# circuitdraft.net
KiCad netlist of a schematic drawn in EAGLE
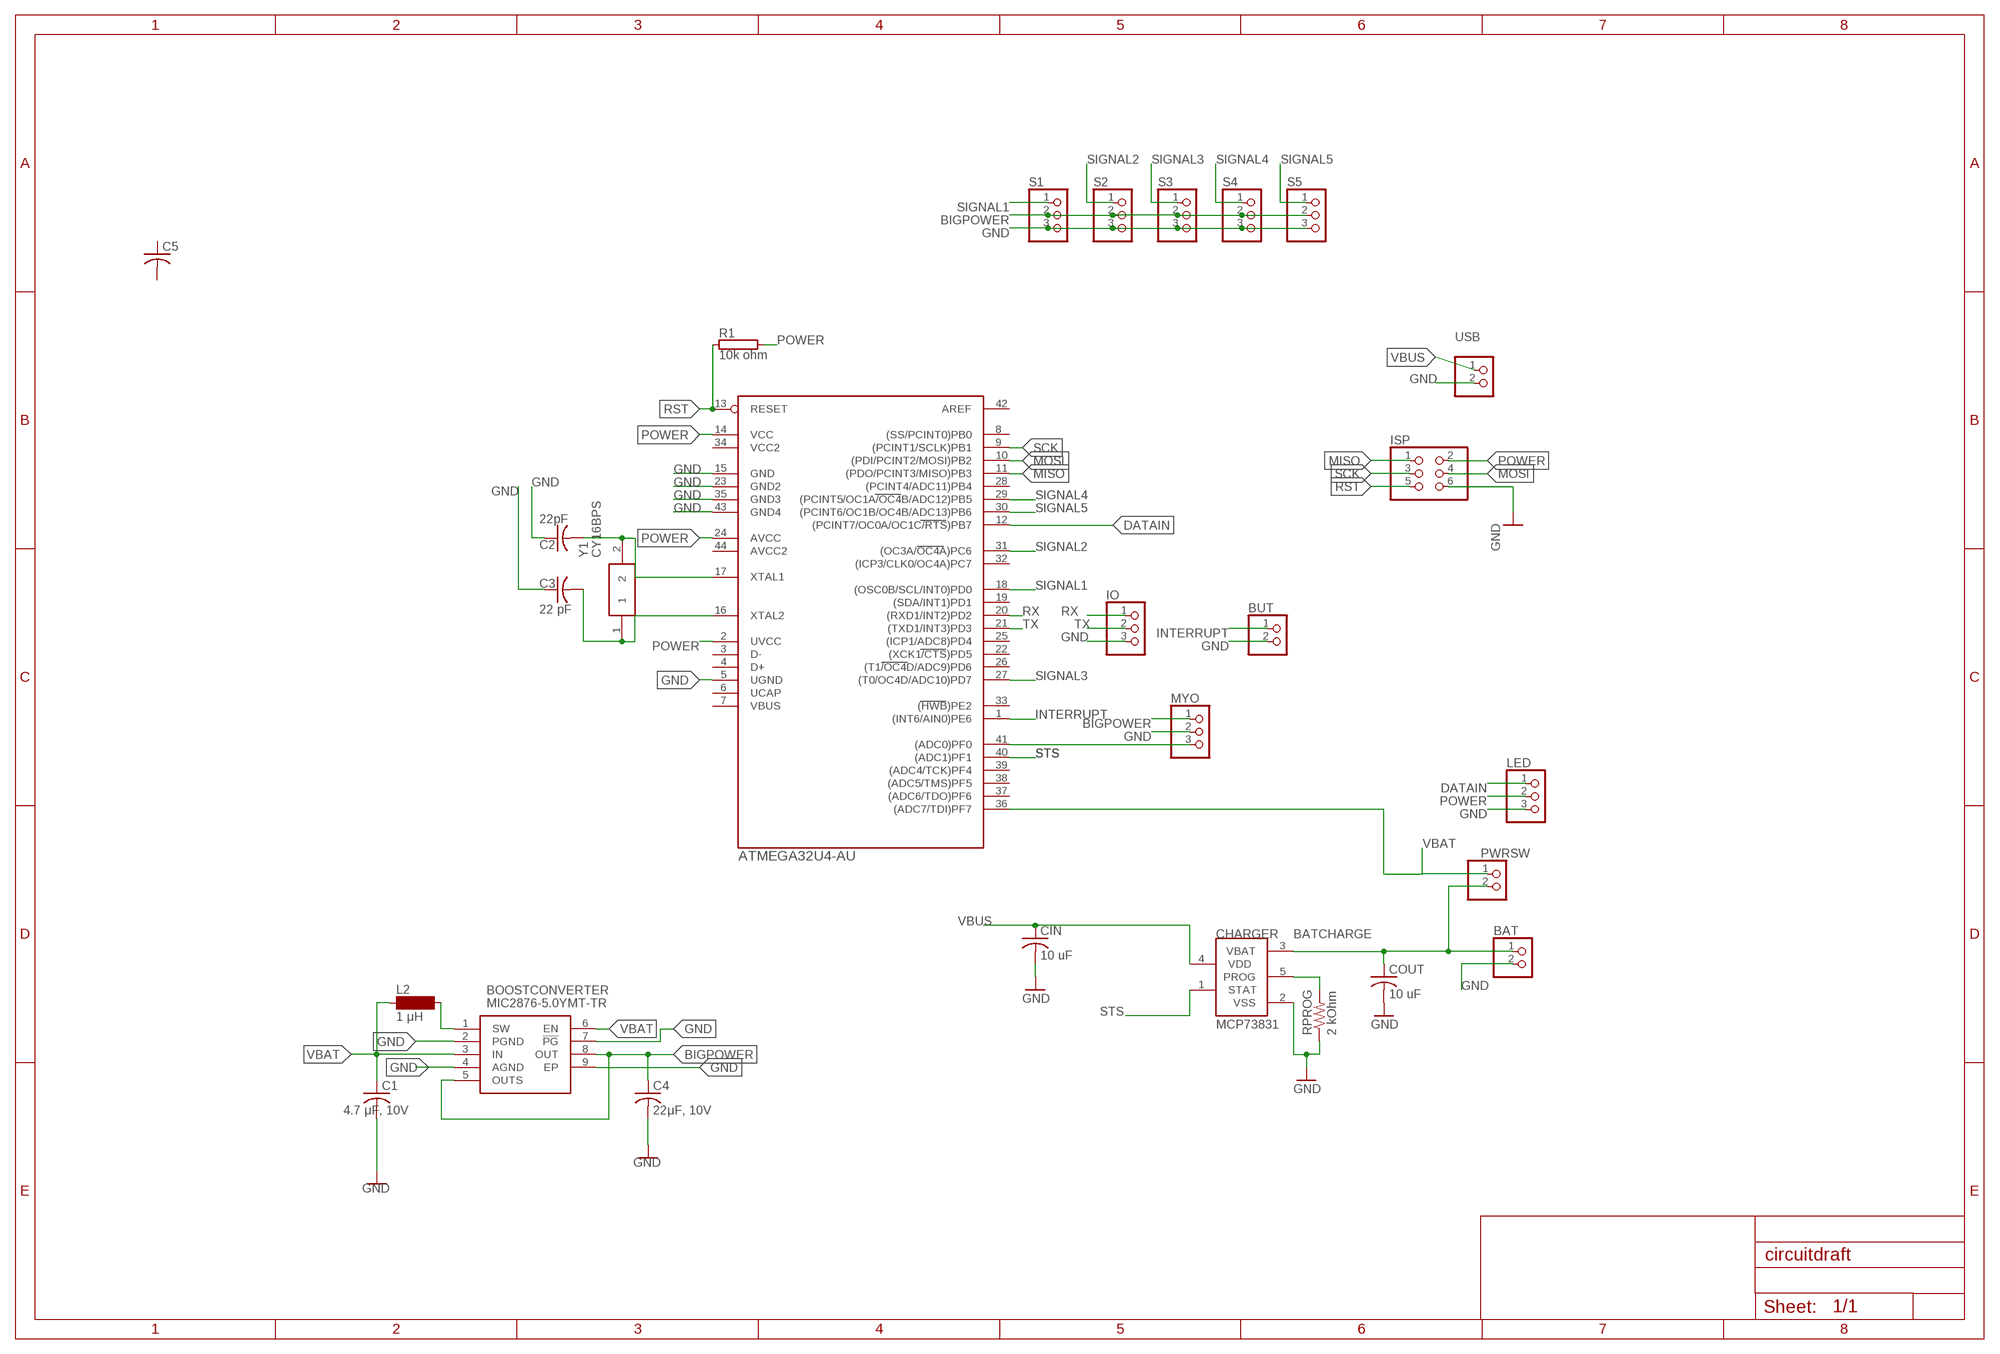
[diagram p0: schematic, sheet 1]

(export (version "E")
  (design (tool "Eeschema 10.0.6"))
  (components
    (comp (ref "BAT")
      (value "PINHD-1X2")
      (footprint "eagle-import:1X02")
      (libsource (lib "eagle-import") (part "PINHD-1X2"))
    )
    (comp (ref "BOOSTCONVERTER")
      (value "MIC2876-5.0YMT-TR")
      (footprint "eagle-import:MIC287650YMTTR")
      (fields (field (name "MOUSER_PART_NUMBER") "998-MIC2876-50YMTTR"))
      (libsource (lib "eagle-import") (part "MIC2876-5.0YMT-TR"))
    )
    (comp (ref "BUT")
      (value "PINHD-1X2")
      (footprint "eagle-import:1X02")
      (libsource (lib "eagle-import") (part "PINHD-1X2"))
    )
    (comp (ref "C1")
      (value "4.7 μF, 10V")
      (footprint "eagle-import:C0603")
      (libsource (lib "eagle-import") (part "C-USC0603"))
    )
    (comp (ref "C2")
      (value "22pF")
      (footprint "eagle-import:C025-024X044")
      (libsource (lib "eagle-import") (part "C-US025-024X044"))
    )
    (comp (ref "C3")
      (value "22 pF")
      (footprint "eagle-import:C025-024X044")
      (libsource (lib "eagle-import") (part "C-US025-024X044"))
    )
    (comp (ref "C4")
      (value "22μF, 10V")
      (footprint "eagle-import:C0603")
      (libsource (lib "eagle-import") (part "C-USC0603"))
    )
    (comp (ref "C5")
      (value "C-USC0603")
      (footprint "eagle-import:C0603")
      (libsource (lib "eagle-import") (part "C-USC0603"))
    )
    (comp (ref "CHARGER")
      (value "MCP73831")
      (footprint "eagle-import:SOT23-5L")
      (libsource (lib "eagle-import") (part "MCP73831"))
    )
    (comp (ref "CIN")
      (value "10 uF")
      (footprint "eagle-import:C0603")
      (libsource (lib "eagle-import") (part "C-USC0603"))
    )
    (comp (ref "COUT")
      (value "10 uF")
      (footprint "eagle-import:C0603")
      (libsource (lib "eagle-import") (part "C-USC0603"))
    )
    (comp (ref "IO")
      (value "PINHD-1X3")
      (footprint "eagle-import:1X03")
      (libsource (lib "eagle-import") (part "PINHD-1X3"))
    )
    (comp (ref "ISP")
      (value "PINHD-2X3")
      (footprint "eagle-import:2X03")
      (libsource (lib "eagle-import") (part "PINHD-2X3"))
    )
    (comp (ref "L2")
      (value "1 μH")
      (footprint "eagle-import:SD75")
      (libsource (lib "eagle-import") (part "SD75"))
    )
    (comp (ref "LED")
      (value "PINHD-1X3")
      (footprint "eagle-import:1X03")
      (libsource (lib "eagle-import") (part "PINHD-1X3"))
    )
    (comp (ref "MYO")
      (value "PINHD-1X3")
      (footprint "eagle-import:1X03")
      (libsource (lib "eagle-import") (part "PINHD-1X3"))
    )
    (comp (ref "PWRSW")
      (value "PINHD-1X2")
      (footprint "eagle-import:1X02")
      (libsource (lib "eagle-import") (part "PINHD-1X2"))
    )
    (comp (ref "R1")
      (value "10k ohm")
      (footprint "eagle-import:RS1_8")
      (libsource (lib "eagle-import") (part "RRS1/8"))
    )
    (comp (ref "RPROG")
      (value "2 kOhm")
      (footprint "eagle-import:R0603")
      (libsource (lib "eagle-import") (part "R-US_R0603"))
    )
    (comp (ref "S1")
      (value "PINHD-1X3")
      (footprint "eagle-import:1X03")
      (libsource (lib "eagle-import") (part "PINHD-1X3"))
    )
    (comp (ref "S2")
      (value "PINHD-1X3")
      (footprint "eagle-import:1X03")
      (libsource (lib "eagle-import") (part "PINHD-1X3"))
    )
    (comp (ref "S3")
      (value "PINHD-1X3")
      (footprint "eagle-import:1X03")
      (libsource (lib "eagle-import") (part "PINHD-1X3"))
    )
    (comp (ref "S4")
      (value "PINHD-1X3")
      (footprint "eagle-import:1X03")
      (libsource (lib "eagle-import") (part "PINHD-1X3"))
    )
    (comp (ref "S5")
      (value "PINHD-1X3")
      (footprint "eagle-import:1X03")
      (libsource (lib "eagle-import") (part "PINHD-1X3"))
    )
    (comp (ref "U$1")
      (value "ATMEGA32U4-AU")
      (footprint "eagle-import:TQFP44")
      (libsource (lib "eagle-import") (part "ATMEGA32U4-AU"))
    )
    (comp (ref "USB")
      (value "PINHD-1X2")
      (footprint "eagle-import:1X02")
      (libsource (lib "eagle-import") (part "PINHD-1X2"))
    )
    (comp (ref "Y1")
      (value "CY16BPS")
      (footprint "eagle-import:CY16BPS")
      (fields (field (name "MOUSER_PART_NUMBER") "549-CY16BPS"))
      (libsource (lib "eagle-import") (part "CY16BPS"))
    )
  )
  (nets
    (net (code "1") (name "/BATCHARGE") (class "Default")
      (node (ref "BAT") (pin "1") (pinfunction "1_1") (pintype "passive"))
      (node (ref "CHARGER") (pin "3") (pinfunction "VBAT_3") (pintype "bidirectional"))
      (node (ref "COUT") (pin "1") (pinfunction "1_1") (pintype "passive"))
      (node (ref "PWRSW") (pin "2") (pinfunction "2_2") (pintype "passive"))
    )
    (net (code "2") (name "/INTERRUPT") (class "Default")
      (node (ref "BUT") (pin "1") (pinfunction "1_1") (pintype "passive"))
      (node (ref "U$1") (pin "1") (pinfunction "(INT6/AIN0)PE6_1") (pintype "bidirectional"))
    )
    (net (code "3") (name "/RX") (class "Default")
      (node (ref "IO") (pin "1") (pinfunction "1_1") (pintype "passive"))
      (node (ref "U$1") (pin "20") (pinfunction "(RXD1/INT2)PD2_20") (pintype "bidirectional"))
    )
    (net (code "4") (name "/SIGNAL1") (class "Default")
      (node (ref "S1") (pin "1") (pinfunction "1_1") (pintype "passive"))
      (node (ref "U$1") (pin "18") (pinfunction "(OSC0B/SCL/INT0)PD0_18") (pintype "bidirectional"))
    )
    (net (code "5") (name "/SIGNAL2") (class "Default")
      (node (ref "S2") (pin "1") (pinfunction "1_1") (pintype "passive"))
      (node (ref "U$1") (pin "31") (pinfunction "(OC3A/OC4A)PC6_31") (pintype "bidirectional"))
    )
    (net (code "6") (name "/SIGNAL3") (class "Default")
      (node (ref "S3") (pin "1") (pinfunction "1_1") (pintype "passive"))
      (node (ref "U$1") (pin "27") (pinfunction "(T0/OC4D/ADC10)PD7_27") (pintype "bidirectional"))
    )
    (net (code "7") (name "/SIGNAL4") (class "Default")
      (node (ref "S4") (pin "1") (pinfunction "1_1") (pintype "passive"))
      (node (ref "U$1") (pin "29") (pinfunction "(PCINT5/OC1A/OC4B/ADC12)PB5_29") (pintype "bidirectional"))
    )
    (net (code "8") (name "/SIGNAL5") (class "Default")
      (node (ref "S5") (pin "1") (pinfunction "1_1") (pintype "passive"))
      (node (ref "U$1") (pin "30") (pinfunction "(PCINT6/OC1B/OC4B/ADC13)PB6_30") (pintype "bidirectional"))
    )
    (net (code "9") (name "/STS") (class "Default")
      (node (ref "CHARGER") (pin "1") (pinfunction "STAT_1") (pintype "bidirectional"))
      (node (ref "U$1") (pin "40") (pinfunction "(ADC1)PF1_40") (pintype "bidirectional"))
    )
    (net (code "10") (name "/TX") (class "Default")
      (node (ref "IO") (pin "2") (pinfunction "2_2") (pintype "passive"))
      (node (ref "U$1") (pin "21") (pinfunction "(TXD1/INT3)PD3_21") (pintype "bidirectional"))
    )
    (net (code "11") (name "BIGPOWER") (class "Default")
      (node (ref "BOOSTCONVERTER") (pin "5") (pinfunction "OUTS_5") (pintype "bidirectional"))
      (node (ref "BOOSTCONVERTER") (pin "8") (pinfunction "OUT_8") (pintype "bidirectional"))
      (node (ref "C4") (pin "1") (pinfunction "1_1") (pintype "passive"))
      (node (ref "MYO") (pin "1") (pinfunction "1_1") (pintype "passive"))
      (node (ref "S1") (pin "2") (pinfunction "2_2") (pintype "passive"))
      (node (ref "S2") (pin "2") (pinfunction "2_2") (pintype "passive"))
      (node (ref "S3") (pin "2") (pinfunction "2_2") (pintype "passive"))
      (node (ref "S4") (pin "2") (pinfunction "2_2") (pintype "passive"))
      (node (ref "S5") (pin "2") (pinfunction "2_2") (pintype "passive"))
    )
    (net (code "12") (name "DATAIN") (class "Default")
      (node (ref "LED") (pin "1") (pinfunction "1_1") (pintype "passive"))
      (node (ref "U$1") (pin "12") (pinfunction "(PCINT7/OC0A/OC1C/RTS)PB7_12") (pintype "bidirectional"))
    )
    (net (code "13") (name "GND") (class "Default")
      (node (ref "BAT") (pin "2") (pinfunction "2_2") (pintype "passive"))
      (node (ref "BOOSTCONVERTER") (pin "2") (pinfunction "PGND_2") (pintype "bidirectional"))
      (node (ref "BOOSTCONVERTER") (pin "4") (pinfunction "AGND_4") (pintype "bidirectional"))
      (node (ref "BOOSTCONVERTER") (pin "7") (pinfunction "~{PG}_7") (pintype "bidirectional"))
      (node (ref "BOOSTCONVERTER") (pin "9") (pinfunction "EP_9") (pintype "bidirectional"))
      (node (ref "BUT") (pin "2") (pinfunction "2_2") (pintype "passive"))
      (node (ref "C1") (pin "2") (pinfunction "2_2") (pintype "passive"))
      (node (ref "C2") (pin "1") (pinfunction "1_1") (pintype "passive"))
      (node (ref "C3") (pin "1") (pinfunction "1_1") (pintype "passive"))
      (node (ref "C4") (pin "2") (pinfunction "2_2") (pintype "passive"))
      (node (ref "CHARGER") (pin "2") (pinfunction "VSS_2") (pintype "bidirectional"))
      (node (ref "CIN") (pin "2") (pinfunction "2_2") (pintype "passive"))
      (node (ref "COUT") (pin "2") (pinfunction "2_2") (pintype "passive"))
      (node (ref "IO") (pin "3") (pinfunction "3_3") (pintype "passive"))
      (node (ref "ISP") (pin "6") (pinfunction "6_6") (pintype "passive"))
      (node (ref "LED") (pin "3") (pinfunction "3_3") (pintype "passive"))
      (node (ref "MYO") (pin "2") (pinfunction "2_2") (pintype "passive"))
      (node (ref "RPROG") (pin "1") (pinfunction "1_1") (pintype "passive"))
      (node (ref "S1") (pin "3") (pinfunction "3_3") (pintype "passive"))
      (node (ref "S2") (pin "3") (pinfunction "3_3") (pintype "passive"))
      (node (ref "S3") (pin "3") (pinfunction "3_3") (pintype "passive"))
      (node (ref "S4") (pin "3") (pinfunction "3_3") (pintype "passive"))
      (node (ref "S5") (pin "3") (pinfunction "3_3") (pintype "passive"))
      (node (ref "U$1") (pin "15") (pinfunction "GND_15") (pintype "bidirectional"))
      (node (ref "U$1") (pin "23") (pinfunction "GND2_23") (pintype "bidirectional"))
      (node (ref "U$1") (pin "35") (pinfunction "GND3_35") (pintype "bidirectional"))
      (node (ref "U$1") (pin "43") (pinfunction "GND4_43") (pintype "bidirectional"))
      (node (ref "U$1") (pin "5") (pinfunction "UGND_5") (pintype "bidirectional"))
      (node (ref "USB") (pin "2") (pinfunction "2_2") (pintype "passive"))
    )
    (net (code "14") (name "MISO") (class "Default")
      (node (ref "ISP") (pin "1") (pinfunction "1_1") (pintype "passive"))
      (node (ref "U$1") (pin "11") (pinfunction "(PDO/PCINT3/MISO)PB3_11") (pintype "bidirectional"))
    )
    (net (code "15") (name "MOSI") (class "Default")
      (node (ref "ISP") (pin "4") (pinfunction "4_4") (pintype "passive"))
      (node (ref "U$1") (pin "10") (pinfunction "(PDI/PCINT2/MOSI)PB2_10") (pintype "bidirectional"))
    )
    (net (code "16") (name "Net-(BOOSTCONVERTER-SW)") (class "Default")
      (node (ref "BOOSTCONVERTER") (pin "1") (pinfunction "SW_1") (pintype "bidirectional"))
      (node (ref "L2") (pin "2") (pinfunction "2_2") (pintype "passive"))
    )
    (net (code "17") (name "Net-(CHARGER-PROG)") (class "Default")
      (node (ref "CHARGER") (pin "5") (pinfunction "PROG_5") (pintype "bidirectional"))
      (node (ref "RPROG") (pin "2") (pinfunction "2_2") (pintype "passive"))
    )
    (net (code "18") (name "Net-(U$1-(ADC0)PF0)") (class "Default")
      (node (ref "MYO") (pin "3") (pinfunction "3_3") (pintype "passive"))
      (node (ref "U$1") (pin "41") (pinfunction "(ADC0)PF0_41") (pintype "bidirectional"))
    )
    (net (code "19") (name "Net-(U$1-XTAL1)") (class "Default")
      (node (ref "C2") (pin "2") (pinfunction "2_2") (pintype "passive"))
      (node (ref "U$1") (pin "17") (pinfunction "XTAL1_17") (pintype "bidirectional"))
      (node (ref "Y1") (pin "2") (pinfunction "2_2") (pintype "bidirectional"))
    )
    (net (code "20") (name "Net-(U$1-XTAL2)") (class "Default")
      (node (ref "C3") (pin "2") (pinfunction "2_2") (pintype "passive"))
      (node (ref "U$1") (pin "16") (pinfunction "XTAL2_16") (pintype "bidirectional"))
      (node (ref "Y1") (pin "1") (pinfunction "1_1") (pintype "bidirectional"))
    )
    (net (code "21") (name "POWER") (class "Default")
      (node (ref "ISP") (pin "2") (pinfunction "2_2") (pintype "passive"))
      (node (ref "LED") (pin "2") (pinfunction "2_2") (pintype "passive"))
      (node (ref "R1") (pin "2") (pinfunction "2_2") (pintype "passive"))
      (node (ref "U$1") (pin "14") (pinfunction "VCC_14") (pintype "bidirectional"))
      (node (ref "U$1") (pin "2") (pinfunction "UVCC_2") (pintype "bidirectional"))
      (node (ref "U$1") (pin "24") (pinfunction "AVCC_24") (pintype "bidirectional"))
    )
    (net (code "22") (name "RST") (class "Default")
      (node (ref "ISP") (pin "5") (pinfunction "5_5") (pintype "passive"))
      (node (ref "R1") (pin "1") (pinfunction "1_1") (pintype "passive"))
      (node (ref "U$1") (pin "13") (pinfunction "RESET_13") (pintype "bidirectional"))
    )
    (net (code "23") (name "SCK") (class "Default")
      (node (ref "ISP") (pin "3") (pinfunction "3_3") (pintype "passive"))
      (node (ref "U$1") (pin "9") (pinfunction "(PCINT1/SCLK)PB1_9") (pintype "bidirectional"))
    )
    (net (code "24") (name "VBAT") (class "Default")
      (node (ref "BOOSTCONVERTER") (pin "3") (pinfunction "IN_3") (pintype "bidirectional"))
      (node (ref "BOOSTCONVERTER") (pin "6") (pinfunction "EN_6") (pintype "bidirectional"))
      (node (ref "C1") (pin "1") (pinfunction "1_1") (pintype "passive"))
      (node (ref "L2") (pin "1") (pinfunction "1_1") (pintype "passive"))
      (node (ref "PWRSW") (pin "1") (pinfunction "1_1") (pintype "passive"))
      (node (ref "U$1") (pin "36") (pinfunction "(ADC7/TDI)PF7_36") (pintype "bidirectional"))
    )
    (net (code "25") (name "VBUS") (class "Default")
      (node (ref "CHARGER") (pin "4") (pinfunction "VDD_4") (pintype "bidirectional"))
      (node (ref "CIN") (pin "1") (pinfunction "1_1") (pintype "passive"))
      (node (ref "USB") (pin "1") (pinfunction "1_1") (pintype "passive"))
    )
    (net (code "26") (name "unconnected-(C5-Pad1)") (class "Default")
      (node (ref "C5") (pin "1") (pinfunction "1_1") (pintype "passive"))
    )
    (net (code "27") (name "unconnected-(C5-Pad2)") (class "Default")
      (node (ref "C5") (pin "2") (pinfunction "2_2") (pintype "passive"))
    )
    (net (code "28") (name "unconnected-(U$1-(ADC4{slash}TCK)PF4-Pad39)") (class "Default")
      (node (ref "U$1") (pin "39") (pinfunction "(ADC4/TCK)PF4_39") (pintype "bidirectional"))
    )
    (net (code "29") (name "unconnected-(U$1-(ADC5{slash}TMS)PF5-Pad38)") (class "Default")
      (node (ref "U$1") (pin "38") (pinfunction "(ADC5/TMS)PF5_38") (pintype "bidirectional"))
    )
    (net (code "30") (name "unconnected-(U$1-(ADC6{slash}TDO)PF6-Pad37)") (class "Default")
      (node (ref "U$1") (pin "37") (pinfunction "(ADC6/TDO)PF6_37") (pintype "bidirectional"))
    )
    (net (code "31") (name "unconnected-(U$1-(HWB)PE2-Pad33)") (class "Default")
      (node (ref "U$1") (pin "33") (pinfunction "(HWB)PE2_33") (pintype "bidirectional"))
    )
    (net (code "32") (name "unconnected-(U$1-(ICP1{slash}ADC8)PD4-Pad25)") (class "Default")
      (node (ref "U$1") (pin "25") (pinfunction "(ICP1/ADC8)PD4_25") (pintype "bidirectional"))
    )
    (net (code "33") (name "unconnected-(U$1-(ICP3{slash}CLK0{slash}OC4A)PC7-Pad32)") (class "Default")
      (node (ref "U$1") (pin "32") (pinfunction "(ICP3/CLK0/OC4A)PC7_32") (pintype "bidirectional"))
    )
    (net (code "34") (name "unconnected-(U$1-(PCINT4{slash}ADC11)PB4-Pad28)") (class "Default")
      (node (ref "U$1") (pin "28") (pinfunction "(PCINT4/ADC11)PB4_28") (pintype "bidirectional"))
    )
    (net (code "35") (name "unconnected-(U$1-(SDA{slash}INT1)PD1-Pad19)") (class "Default")
      (node (ref "U$1") (pin "19") (pinfunction "(SDA/INT1)PD1_19") (pintype "bidirectional"))
    )
    (net (code "36") (name "unconnected-(U$1-(SS{slash}PCINT0)PB0-Pad8)") (class "Default")
      (node (ref "U$1") (pin "8") (pinfunction "(SS/PCINT0)PB0_8") (pintype "bidirectional"))
    )
    (net (code "37") (name "unconnected-(U$1-(T1{slash}OC4D{slash}ADC9)PD6-Pad26)") (class "Default")
      (node (ref "U$1") (pin "26") (pinfunction "(T1/OC4D/ADC9)PD6_26") (pintype "bidirectional"))
    )
    (net (code "38") (name "unconnected-(U$1-(XCK1{slash}CTS)PD5-Pad22)") (class "Default")
      (node (ref "U$1") (pin "22") (pinfunction "(XCK1/CTS)PD5_22") (pintype "bidirectional"))
    )
    (net (code "39") (name "unconnected-(U$1-AREF-Pad42)") (class "Default")
      (node (ref "U$1") (pin "42") (pinfunction "AREF_42") (pintype "bidirectional"))
    )
    (net (code "40") (name "unconnected-(U$1-AVCC2-Pad44)") (class "Default")
      (node (ref "U$1") (pin "44") (pinfunction "AVCC2_44") (pintype "bidirectional"))
    )
    (net (code "41") (name "unconnected-(U$1-D+-Pad4)") (class "Default")
      (node (ref "U$1") (pin "4") (pinfunction "D+_4") (pintype "bidirectional"))
    )
    (net (code "42") (name "unconnected-(U$1-D--Pad3)") (class "Default")
      (node (ref "U$1") (pin "3") (pinfunction "D-_3") (pintype "bidirectional"))
    )
    (net (code "43") (name "unconnected-(U$1-UCAP-Pad6)") (class "Default")
      (node (ref "U$1") (pin "6") (pinfunction "UCAP_6") (pintype "bidirectional"))
    )
    (net (code "44") (name "unconnected-(U$1-VBUS-Pad7)") (class "Default")
      (node (ref "U$1") (pin "7") (pinfunction "VBUS_7") (pintype "bidirectional"))
    )
    (net (code "45") (name "unconnected-(U$1-VCC2-Pad34)") (class "Default")
      (node (ref "U$1") (pin "34") (pinfunction "VCC2_34") (pintype "bidirectional"))
    )
  )
)
